# murdock_conn.net
KiCad netlist of a schematic drawn in EAGLE
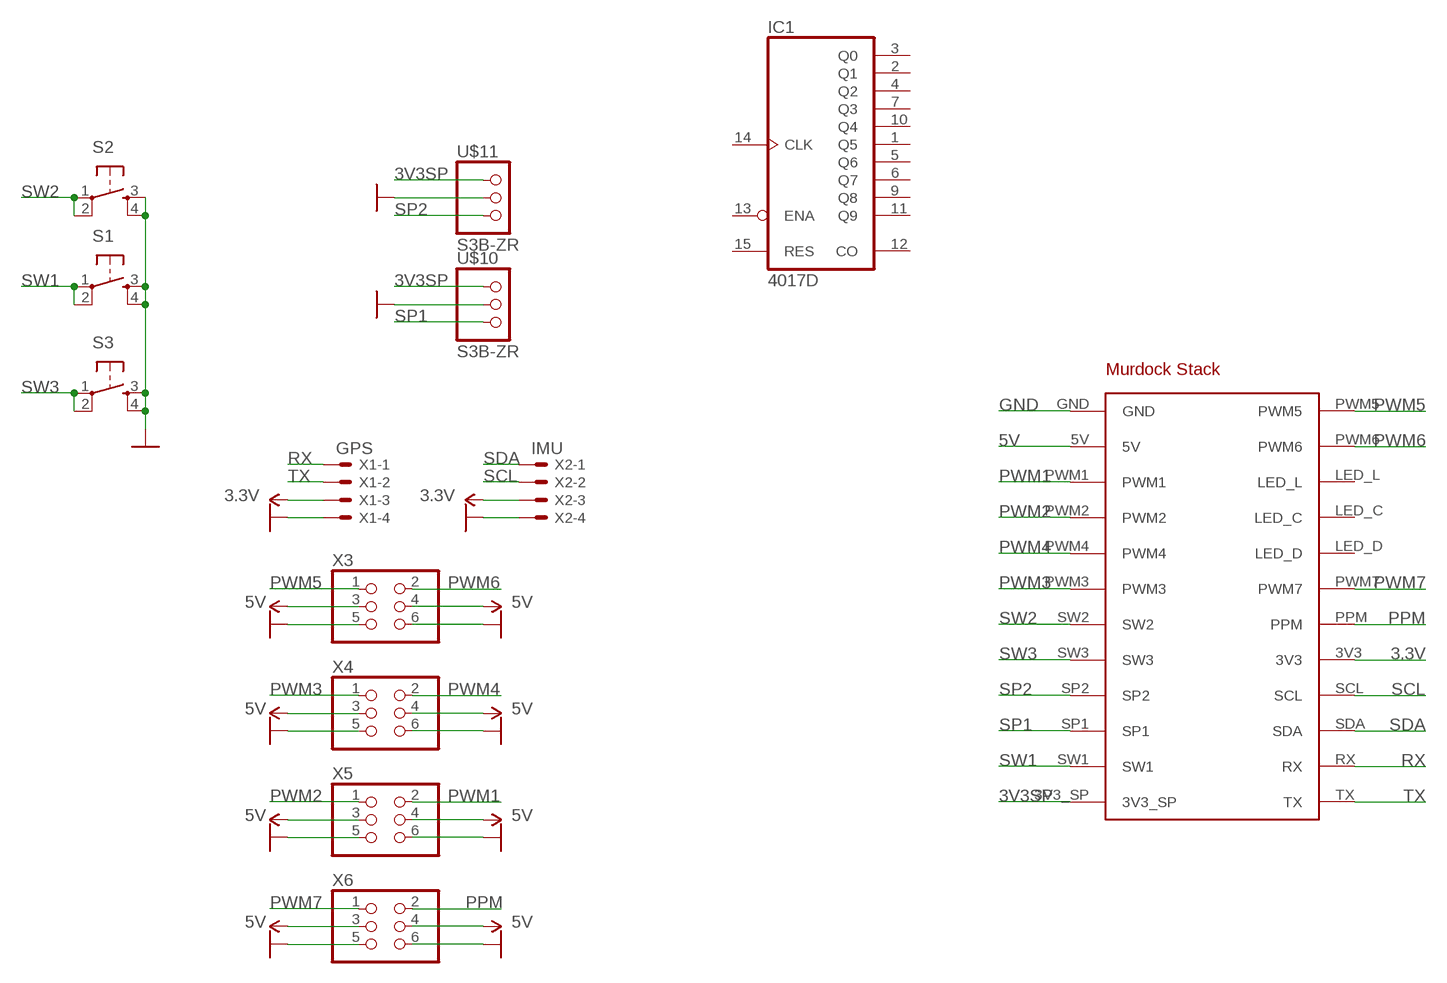
[diagram p0: schematic, sheet 1]

(export (version "E")
  (design (tool "Eeschema 10.0.6"))
  (components
    (comp (ref "IC1")
      (value "4017D")
      (footprint "eagle-import:SO16")
      (libsource (lib "eagle-import") (part "4017D"))
    )
    (comp (ref "S1")
      (value "LSH")
      (footprint "eagle-import:LSH")
      (libsource (lib "eagle-import") (part "LSH"))
    )
    (comp (ref "S2")
      (value "LSH")
      (footprint "eagle-import:LSH")
      (libsource (lib "eagle-import") (part "LSH"))
    )
    (comp (ref "S3")
      (value "LSH")
      (footprint "eagle-import:LSH")
      (libsource (lib "eagle-import") (part "LSH"))
    )
    (comp (ref "U$10")
      (value "S3B-ZR")
      (footprint "eagle-import:S3B-ZR")
      (libsource (lib "eagle-import") (part "S3B-ZR"))
    )
    (comp (ref "U$11")
      (value "S3B-ZR")
      (footprint "eagle-import:S3B-ZR")
      (libsource (lib "eagle-import") (part "S3B-ZR"))
    )
    (comp (ref "X1")
      (value "GPS")
      (footprint "eagle-import:70553-04")
      (libsource (lib "eagle-import") (part "C-GRID-04-70553"))
    )
    (comp (ref "X2")
      (value "IMU")
      (footprint "eagle-import:70553-04")
      (libsource (lib "eagle-import") (part "C-GRID-04-70553"))
    )
    (comp (ref "X3")
      (value "PINHD-2X3/90")
      (footprint "eagle-import:2X03_90")
      (libsource (lib "eagle-import") (part "PINHD-2X3/90"))
    )
    (comp (ref "X4")
      (value "PINHD-2X3/90")
      (footprint "eagle-import:2X03_90")
      (libsource (lib "eagle-import") (part "PINHD-2X3/90"))
    )
    (comp (ref "X5")
      (value "PINHD-2X3/90")
      (footprint "eagle-import:2X03_90")
      (libsource (lib "eagle-import") (part "PINHD-2X3/90"))
    )
    (comp (ref "X6")
      (value "PINHD-2X3/90")
      (footprint "eagle-import:2X03_90")
      (libsource (lib "eagle-import") (part "PINHD-2X3/90"))
    )
    (comp (ref "X7")
      (value "MURDOCK_STACK")
      (footprint "eagle-import:MURDOCK_STACK")
      (libsource (lib "eagle-import") (part "MURDOCK_STACK"))
    )
  )
  (nets
    (net (code "1") (name "/3V3SP") (class "Default")
      (node (ref "U$10") (pin "1") (pinfunction "1_1") (pintype "bidirectional"))
      (node (ref "U$11") (pin "1") (pinfunction "1_1") (pintype "bidirectional"))
      (node (ref "X7") (pin "3V3_SP") (pinfunction "3V3_SP_3V3_SP") (pintype "bidirectional"))
    )
    (net (code "2") (name "/PPM") (class "Default")
      (node (ref "X6") (pin "2") (pinfunction "2_2") (pintype "passive"))
      (node (ref "X7") (pin "PPM") (pinfunction "PPM_PPM") (pintype "bidirectional"))
    )
    (net (code "3") (name "/PWM1") (class "Default")
      (node (ref "X5") (pin "2") (pinfunction "2_2") (pintype "passive"))
      (node (ref "X7") (pin "PWM1") (pinfunction "PWM1_PWM1") (pintype "bidirectional"))
    )
    (net (code "4") (name "/PWM2") (class "Default")
      (node (ref "X5") (pin "1") (pinfunction "1_1") (pintype "passive"))
      (node (ref "X7") (pin "PWM2") (pinfunction "PWM2_PWM2") (pintype "bidirectional"))
    )
    (net (code "5") (name "/PWM3") (class "Default")
      (node (ref "X4") (pin "1") (pinfunction "1_1") (pintype "passive"))
      (node (ref "X7") (pin "PWM3") (pinfunction "PWM3_PWM3") (pintype "bidirectional"))
    )
    (net (code "6") (name "/PWM4") (class "Default")
      (node (ref "X4") (pin "2") (pinfunction "2_2") (pintype "passive"))
      (node (ref "X7") (pin "PWM4") (pinfunction "PWM4_PWM4") (pintype "bidirectional"))
    )
    (net (code "7") (name "/PWM5") (class "Default")
      (node (ref "X3") (pin "1") (pinfunction "1_1") (pintype "passive"))
      (node (ref "X7") (pin "PWM5") (pinfunction "PWM5_PWM5") (pintype "bidirectional"))
    )
    (net (code "8") (name "/PWM6") (class "Default")
      (node (ref "X3") (pin "2") (pinfunction "2_2") (pintype "passive"))
      (node (ref "X7") (pin "PWM6") (pinfunction "PWM6_PWM6") (pintype "bidirectional"))
    )
    (net (code "9") (name "/PWM7") (class "Default")
      (node (ref "X6") (pin "1") (pinfunction "1_1") (pintype "passive"))
      (node (ref "X7") (pin "PWM7") (pinfunction "PWM7_PWM7") (pintype "bidirectional"))
    )
    (net (code "10") (name "/RX") (class "Default")
      (node (ref "X1") (pin "1") (pinfunction "S_1") (pintype "passive"))
      (node (ref "X7") (pin "RX") (pinfunction "RX_RX") (pintype "bidirectional"))
    )
    (net (code "11") (name "/SCL") (class "Default")
      (node (ref "X2") (pin "2") (pinfunction "S_2") (pintype "passive"))
      (node (ref "X7") (pin "SCL") (pinfunction "SCL_SCL") (pintype "bidirectional"))
    )
    (net (code "12") (name "/SDA") (class "Default")
      (node (ref "X2") (pin "1") (pinfunction "S_1") (pintype "passive"))
      (node (ref "X7") (pin "SDA") (pinfunction "SDA_SDA") (pintype "bidirectional"))
    )
    (net (code "13") (name "/SP1") (class "Default")
      (node (ref "U$10") (pin "3") (pinfunction "3_3") (pintype "bidirectional"))
      (node (ref "X7") (pin "SP1") (pinfunction "SP1_SP1") (pintype "bidirectional"))
    )
    (net (code "14") (name "/SP2") (class "Default")
      (node (ref "U$11") (pin "3") (pinfunction "3_3") (pintype "bidirectional"))
      (node (ref "X7") (pin "SP2") (pinfunction "SP2_SP2") (pintype "bidirectional"))
    )
    (net (code "15") (name "/SW1") (class "Default")
      (node (ref "S1") (pin "1") (pinfunction "1_1") (pintype "passive"))
      (node (ref "S1") (pin "2") (pinfunction "2_2") (pintype "passive"))
      (node (ref "X7") (pin "SW1") (pinfunction "SW1_SW1") (pintype "bidirectional"))
    )
    (net (code "16") (name "/SW2") (class "Default")
      (node (ref "S2") (pin "1") (pinfunction "1_1") (pintype "passive"))
      (node (ref "S2") (pin "2") (pinfunction "2_2") (pintype "passive"))
      (node (ref "X7") (pin "SW2") (pinfunction "SW2_SW2") (pintype "bidirectional"))
    )
    (net (code "17") (name "/SW3") (class "Default")
      (node (ref "S3") (pin "1") (pinfunction "1_1") (pintype "passive"))
      (node (ref "S3") (pin "2") (pinfunction "2_2") (pintype "passive"))
      (node (ref "X7") (pin "SW3") (pinfunction "SW3_SW3") (pintype "bidirectional"))
    )
    (net (code "18") (name "/TX") (class "Default")
      (node (ref "X1") (pin "2") (pinfunction "S_2") (pintype "passive"))
      (node (ref "X7") (pin "TX") (pinfunction "TX_TX") (pintype "bidirectional"))
    )
    (net (code "19") (name "3.3V") (class "Default")
      (node (ref "X1") (pin "3") (pinfunction "S_3") (pintype "passive"))
      (node (ref "X2") (pin "3") (pinfunction "S_3") (pintype "passive"))
      (node (ref "X7") (pin "3V3") (pinfunction "3V3_3V3") (pintype "bidirectional"))
    )
    (net (code "20") (name "5V") (class "Default")
      (node (ref "X3") (pin "3") (pinfunction "3_3") (pintype "passive"))
      (node (ref "X3") (pin "4") (pinfunction "4_4") (pintype "passive"))
      (node (ref "X4") (pin "3") (pinfunction "3_3") (pintype "passive"))
      (node (ref "X4") (pin "4") (pinfunction "4_4") (pintype "passive"))
      (node (ref "X5") (pin "3") (pinfunction "3_3") (pintype "passive"))
      (node (ref "X5") (pin "4") (pinfunction "4_4") (pintype "passive"))
      (node (ref "X6") (pin "3") (pinfunction "3_3") (pintype "passive"))
      (node (ref "X6") (pin "4") (pinfunction "4_4") (pintype "passive"))
      (node (ref "X7") (pin "5V") (pinfunction "5V_5V") (pintype "bidirectional"))
    )
    (net (code "21") (name "GND") (class "Default")
      (node (ref "S1") (pin "3") (pinfunction "3_3") (pintype "passive"))
      (node (ref "S1") (pin "4") (pinfunction "4_4") (pintype "passive"))
      (node (ref "S2") (pin "3") (pinfunction "3_3") (pintype "passive"))
      (node (ref "S2") (pin "4") (pinfunction "4_4") (pintype "passive"))
      (node (ref "S3") (pin "3") (pinfunction "3_3") (pintype "passive"))
      (node (ref "S3") (pin "4") (pinfunction "4_4") (pintype "passive"))
      (node (ref "U$10") (pin "2") (pinfunction "2_2") (pintype "bidirectional"))
      (node (ref "U$11") (pin "2") (pinfunction "2_2") (pintype "bidirectional"))
      (node (ref "X1") (pin "4") (pinfunction "S_4") (pintype "passive"))
      (node (ref "X2") (pin "4") (pinfunction "S_4") (pintype "passive"))
      (node (ref "X3") (pin "5") (pinfunction "5_5") (pintype "passive"))
      (node (ref "X3") (pin "6") (pinfunction "6_6") (pintype "passive"))
      (node (ref "X4") (pin "5") (pinfunction "5_5") (pintype "passive"))
      (node (ref "X4") (pin "6") (pinfunction "6_6") (pintype "passive"))
      (node (ref "X5") (pin "5") (pinfunction "5_5") (pintype "passive"))
      (node (ref "X5") (pin "6") (pinfunction "6_6") (pintype "passive"))
      (node (ref "X6") (pin "5") (pinfunction "5_5") (pintype "passive"))
      (node (ref "X6") (pin "6") (pinfunction "6_6") (pintype "passive"))
      (node (ref "X7") (pin "GND") (pinfunction "GND_GND") (pintype "bidirectional"))
    )
    (net (code "22") (name "unconnected-(IC1A-CLK-Pad14)") (class "Default")
      (node (ref "IC1") (pin "14") (pinfunction "CLK_14") (pintype "input"))
    )
    (net (code "23") (name "unconnected-(IC1A-CO-Pad12)") (class "Default")
      (node (ref "IC1") (pin "12") (pinfunction "CO_12") (pintype "output"))
    )
    (net (code "24") (name "unconnected-(IC1A-ENA-Pad13)") (class "Default")
      (node (ref "IC1") (pin "13") (pinfunction "ENA_13") (pintype "input"))
    )
    (net (code "25") (name "unconnected-(IC1A-Q0-Pad3)") (class "Default")
      (node (ref "IC1") (pin "3") (pinfunction "Q0_3") (pintype "output"))
    )
    (net (code "26") (name "unconnected-(IC1A-Q1-Pad2)") (class "Default")
      (node (ref "IC1") (pin "2") (pinfunction "Q1_2") (pintype "output"))
    )
    (net (code "27") (name "unconnected-(IC1A-Q2-Pad4)") (class "Default")
      (node (ref "IC1") (pin "4") (pinfunction "Q2_4") (pintype "output"))
    )
    (net (code "28") (name "unconnected-(IC1A-Q3-Pad7)") (class "Default")
      (node (ref "IC1") (pin "7") (pinfunction "Q3_7") (pintype "output"))
    )
    (net (code "29") (name "unconnected-(IC1A-Q4-Pad10)") (class "Default")
      (node (ref "IC1") (pin "10") (pinfunction "Q4_10") (pintype "output"))
    )
    (net (code "30") (name "unconnected-(IC1A-Q5-Pad1)") (class "Default")
      (node (ref "IC1") (pin "1") (pinfunction "Q5_1") (pintype "output"))
    )
    (net (code "31") (name "unconnected-(IC1A-Q6-Pad5)") (class "Default")
      (node (ref "IC1") (pin "5") (pinfunction "Q6_5") (pintype "output"))
    )
    (net (code "32") (name "unconnected-(IC1A-Q7-Pad6)") (class "Default")
      (node (ref "IC1") (pin "6") (pinfunction "Q7_6") (pintype "output"))
    )
    (net (code "33") (name "unconnected-(IC1A-Q8-Pad9)") (class "Default")
      (node (ref "IC1") (pin "9") (pinfunction "Q8_9") (pintype "output"))
    )
    (net (code "34") (name "unconnected-(IC1A-Q9-Pad11)") (class "Default")
      (node (ref "IC1") (pin "11") (pinfunction "Q9_11") (pintype "output"))
    )
    (net (code "35") (name "unconnected-(IC1A-RES-Pad15)") (class "Default")
      (node (ref "IC1") (pin "15") (pinfunction "RES_15") (pintype "input"))
    )
    (net (code "36") (name "unconnected-(X7-PadLED_C)") (class "Default")
      (node (ref "X7") (pin "LED_C") (pinfunction "LED_C_LED_C") (pintype "bidirectional"))
    )
    (net (code "37") (name "unconnected-(X7-PadLED_D)") (class "Default")
      (node (ref "X7") (pin "LED_D") (pinfunction "LED_D_LED_D") (pintype "bidirectional"))
    )
    (net (code "38") (name "unconnected-(X7-PadLED_L)") (class "Default")
      (node (ref "X7") (pin "LED_L") (pinfunction "LED_L_LED_L") (pintype "bidirectional"))
    )
  )
)
